# arm_femur_wLED.net
KiCad netlist of a schematic drawn in EAGLE
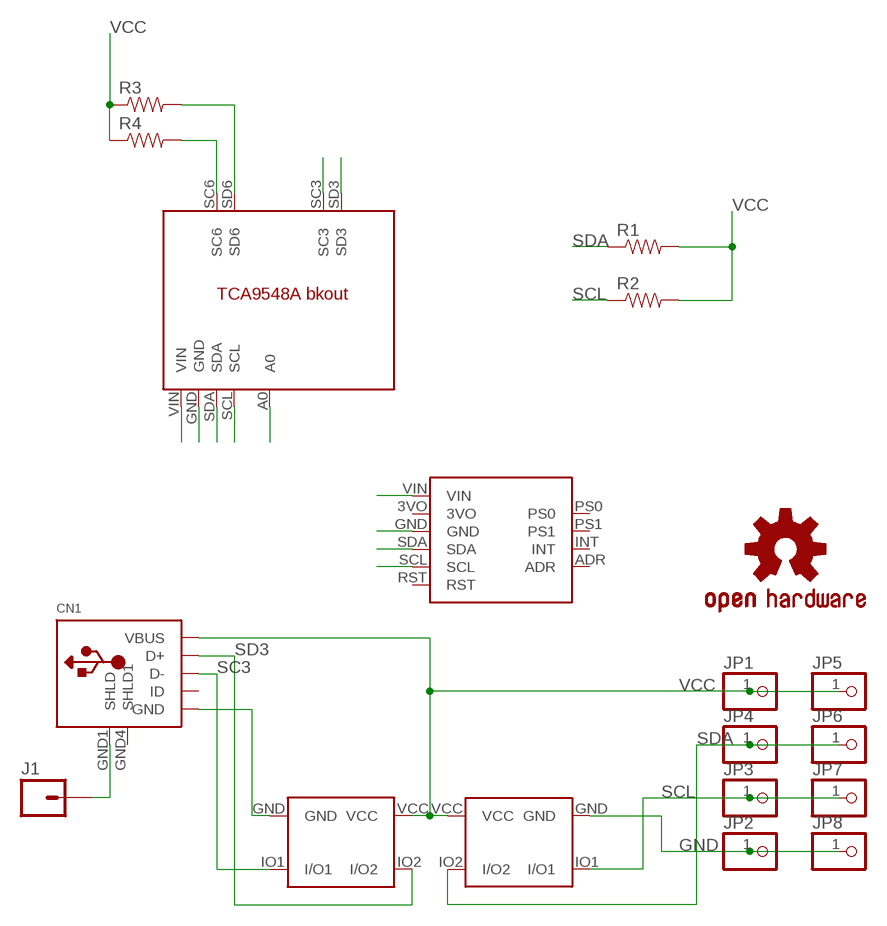
[diagram p0: schematic, sheet 1]

(export (version "E")
  (design (tool "Eeschema 10.0.6"))
  (components
    (comp (ref "CN1")
      (value "USB")
      (footprint "eagle-import:USB-MINIB-THM-MOLEX_NOSLK")
      (libsource (lib "eagle-import") (part "USB"))
    )
    (comp (ref "J1")
      (value "M01PTH")
      (footprint "eagle-import:1X01")
      (libsource (lib "eagle-import") (part "M01PTH"))
    )
    (comp (ref "JP1")
      (value "PINHD-1X1CB")
      (footprint "eagle-import:1X01-CLEANBIG")
      (libsource (lib "eagle-import") (part "PINHD-1X1CB"))
    )
    (comp (ref "JP2")
      (value "PINHD-1X1CB")
      (footprint "eagle-import:1X01-CLEANBIG")
      (libsource (lib "eagle-import") (part "PINHD-1X1CB"))
    )
    (comp (ref "JP3")
      (value "PINHD-1X1CB")
      (footprint "eagle-import:1X01-CLEANBIG")
      (libsource (lib "eagle-import") (part "PINHD-1X1CB"))
    )
    (comp (ref "JP4")
      (value "PINHD-1X1CB")
      (footprint "eagle-import:1X01-CLEANBIG")
      (libsource (lib "eagle-import") (part "PINHD-1X1CB"))
    )
    (comp (ref "JP5")
      (value "PINHD-1X1CB")
      (footprint "eagle-import:1X01-CLEANBIG")
      (libsource (lib "eagle-import") (part "PINHD-1X1CB"))
    )
    (comp (ref "JP6")
      (value "PINHD-1X1CB")
      (footprint "eagle-import:1X01-CLEANBIG")
      (libsource (lib "eagle-import") (part "PINHD-1X1CB"))
    )
    (comp (ref "JP7")
      (value "PINHD-1X1CB")
      (footprint "eagle-import:1X01-CLEANBIG")
      (libsource (lib "eagle-import") (part "PINHD-1X1CB"))
    )
    (comp (ref "JP8")
      (value "PINHD-1X1CB")
      (footprint "eagle-import:1X01-CLEANBIG")
      (libsource (lib "eagle-import") (part "PINHD-1X1CB"))
    )
    (comp (ref "LOGO1")
      (value "OSHW-LOGOM")
      (footprint "eagle-import:OSHW-LOGO-M")
      (libsource (lib "eagle-import") (part "OSHW-LOGOM"))
    )
    (comp (ref "R1")
      (value "RESISTORAXIAL-0.3")
      (footprint "eagle-import:AXIAL-0.3")
      (libsource (lib "eagle-import") (part "RESISTORAXIAL-0.3"))
    )
    (comp (ref "R2")
      (value "RESISTORAXIAL-0.3")
      (footprint "eagle-import:AXIAL-0.3")
      (libsource (lib "eagle-import") (part "RESISTORAXIAL-0.3"))
    )
    (comp (ref "R3")
      (value "RESISTORAXIAL-0.3")
      (footprint "eagle-import:AXIAL-0.3")
      (libsource (lib "eagle-import") (part "RESISTORAXIAL-0.3"))
    )
    (comp (ref "R4")
      (value "RESISTORAXIAL-0.3")
      (footprint "eagle-import:AXIAL-0.3")
      (libsource (lib "eagle-import") (part "RESISTORAXIAL-0.3"))
    )
    (comp (ref "U$1")
      (value "BNO_055_BKOUT")
      (footprint "eagle-import:BNO_BKOUT")
      (libsource (lib "eagle-import") (part "BNO_055_BKOUT"))
    )
    (comp (ref "U$2")
      (value "TCA9548_ARM_FEMUR")
      (footprint "eagle-import:TCA9548_ARM_FEMUR")
      (libsource (lib "eagle-import") (part "TCA9548_ARM_FEMUR"))
    )
    (comp (ref "U$3")
      (value "TVS_ARRAY_CD143A")
      (footprint "eagle-import:SOT-143")
      (libsource (lib "eagle-import") (part "TVS_ARRAY_CD143A"))
    )
    (comp (ref "U$4")
      (value "TVS_ARRAY_CD143A")
      (footprint "eagle-import:SOT-143")
      (libsource (lib "eagle-import") (part "TVS_ARRAY_CD143A"))
    )
  )
  (nets
    (net (code "1") (name "/GND") (class "Default")
      (node (ref "CN1") (pin "GND") (pinfunction "GND_GND") (pintype "power_in"))
      (node (ref "JP2") (pin "1") (pinfunction "1_1") (pintype "passive"))
      (node (ref "JP8") (pin "1") (pinfunction "1_1") (pintype "passive"))
      (node (ref "U$1") (pin "GND") (pinfunction "GND_GND") (pintype "bidirectional"))
      (node (ref "U$2") (pin "GND") (pinfunction "GND_GND") (pintype "bidirectional"))
      (node (ref "U$3") (pin "GND") (pinfunction "GND_GND") (pintype "power_in"))
      (node (ref "U$4") (pin "GND") (pinfunction "GND_GND") (pintype "power_in"))
    )
    (net (code "2") (name "/SC3") (class "Default")
      (node (ref "CN1") (pin "D-") (pinfunction "D-_D-") (pintype "bidirectional"))
      (node (ref "U$2") (pin "SC3") (pinfunction "SC3_SC3") (pintype "bidirectional"))
      (node (ref "U$4") (pin "IO1") (pinfunction "I/O1_IO1") (pintype "bidirectional"))
    )
    (net (code "3") (name "/SC6") (class "Default")
      (node (ref "R4") (pin "P$2") (pinfunction "2_P$2") (pintype "passive"))
      (node (ref "U$1") (pin "SCL") (pinfunction "SCL_SCL") (pintype "bidirectional"))
      (node (ref "U$2") (pin "SC6") (pinfunction "SC6_SC6") (pintype "bidirectional"))
    )
    (net (code "4") (name "/SCL") (class "Default")
      (node (ref "JP3") (pin "1") (pinfunction "1_1") (pintype "passive"))
      (node (ref "JP7") (pin "1") (pinfunction "1_1") (pintype "passive"))
      (node (ref "R2") (pin "P$1") (pinfunction "1_P$1") (pintype "passive"))
      (node (ref "U$2") (pin "SCL") (pinfunction "SCL_SCL") (pintype "bidirectional"))
      (node (ref "U$3") (pin "IO1") (pinfunction "I/O1_IO1") (pintype "bidirectional"))
    )
    (net (code "5") (name "/SD3") (class "Default")
      (node (ref "CN1") (pin "D+") (pinfunction "D+_D+") (pintype "bidirectional"))
      (node (ref "U$2") (pin "SD3") (pinfunction "SD3_SD3") (pintype "bidirectional"))
      (node (ref "U$4") (pin "IO2") (pinfunction "I/O2_IO2") (pintype "bidirectional"))
    )
    (net (code "6") (name "/SD6") (class "Default")
      (node (ref "R3") (pin "P$2") (pinfunction "2_P$2") (pintype "passive"))
      (node (ref "U$1") (pin "SDA") (pinfunction "SDA_SDA") (pintype "bidirectional"))
      (node (ref "U$2") (pin "SD6") (pinfunction "SD6_SD6") (pintype "bidirectional"))
    )
    (net (code "7") (name "/SDA") (class "Default")
      (node (ref "JP4") (pin "1") (pinfunction "1_1") (pintype "passive"))
      (node (ref "JP6") (pin "1") (pinfunction "1_1") (pintype "passive"))
      (node (ref "R1") (pin "P$1") (pinfunction "1_P$1") (pintype "passive"))
      (node (ref "U$2") (pin "SDA") (pinfunction "SDA_SDA") (pintype "bidirectional"))
      (node (ref "U$3") (pin "IO2") (pinfunction "I/O2_IO2") (pintype "bidirectional"))
    )
    (net (code "8") (name "/VCC") (class "Default")
      (node (ref "CN1") (pin "VBUS") (pinfunction "VBUS_VBUS") (pintype "power_in"))
      (node (ref "JP1") (pin "1") (pinfunction "1_1") (pintype "passive"))
      (node (ref "JP5") (pin "1") (pinfunction "1_1") (pintype "passive"))
      (node (ref "R1") (pin "P$2") (pinfunction "2_P$2") (pintype "passive"))
      (node (ref "R2") (pin "P$2") (pinfunction "2_P$2") (pintype "passive"))
      (node (ref "R3") (pin "P$1") (pinfunction "1_P$1") (pintype "passive"))
      (node (ref "R4") (pin "P$1") (pinfunction "1_P$1") (pintype "passive"))
      (node (ref "U$1") (pin "VIN") (pinfunction "VIN_VIN") (pintype "bidirectional"))
      (node (ref "U$2") (pin "A0") (pinfunction "A0_A0") (pintype "bidirectional"))
      (node (ref "U$2") (pin "VIN") (pinfunction "VIN_VIN") (pintype "bidirectional"))
      (node (ref "U$3") (pin "VCC") (pinfunction "VCC_VCC") (pintype "power_in"))
      (node (ref "U$4") (pin "VCC") (pinfunction "VCC_VCC") (pintype "power_in"))
    )
    (net (code "9") (name "Net-(CN1-SHLD)") (class "Default")
      (node (ref "CN1") (pin "GND1") (pinfunction "SHLD_GND1") (pintype "bidirectional"))
      (node (ref "J1") (pin "1") (pinfunction "1_1") (pintype "passive"))
    )
    (net (code "10") (name "unconnected-(CN1-PadID)") (class "Default")
      (node (ref "CN1") (pin "ID") (pinfunction "ID_ID") (pintype "bidirectional"))
    )
    (net (code "11") (name "unconnected-(CN1-SHLD1-PadGND4)") (class "Default")
      (node (ref "CN1") (pin "GND4") (pinfunction "SHLD1_GND4") (pintype "bidirectional"))
    )
    (net (code "12") (name "unconnected-(U$1-Pad3VO)") (class "Default")
      (node (ref "U$1") (pin "3VO") (pinfunction "3VO_3VO") (pintype "bidirectional"))
    )
    (net (code "13") (name "unconnected-(U$1-PadADR)") (class "Default")
      (node (ref "U$1") (pin "ADR") (pinfunction "ADR_ADR") (pintype "bidirectional"))
    )
    (net (code "14") (name "unconnected-(U$1-PadINT)") (class "Default")
      (node (ref "U$1") (pin "INT") (pinfunction "INT_INT") (pintype "bidirectional"))
    )
    (net (code "15") (name "unconnected-(U$1-PadPS0)") (class "Default")
      (node (ref "U$1") (pin "PS0") (pinfunction "PS0_PS0") (pintype "bidirectional"))
    )
    (net (code "16") (name "unconnected-(U$1-PadPS1)") (class "Default")
      (node (ref "U$1") (pin "PS1") (pinfunction "PS1_PS1") (pintype "bidirectional"))
    )
    (net (code "17") (name "unconnected-(U$1-PadRST)") (class "Default")
      (node (ref "U$1") (pin "RST") (pinfunction "RST_RST") (pintype "bidirectional"))
    )
  )
)
